# LinkS.net
KiCad netlist of a schematic drawn in Altium Designer
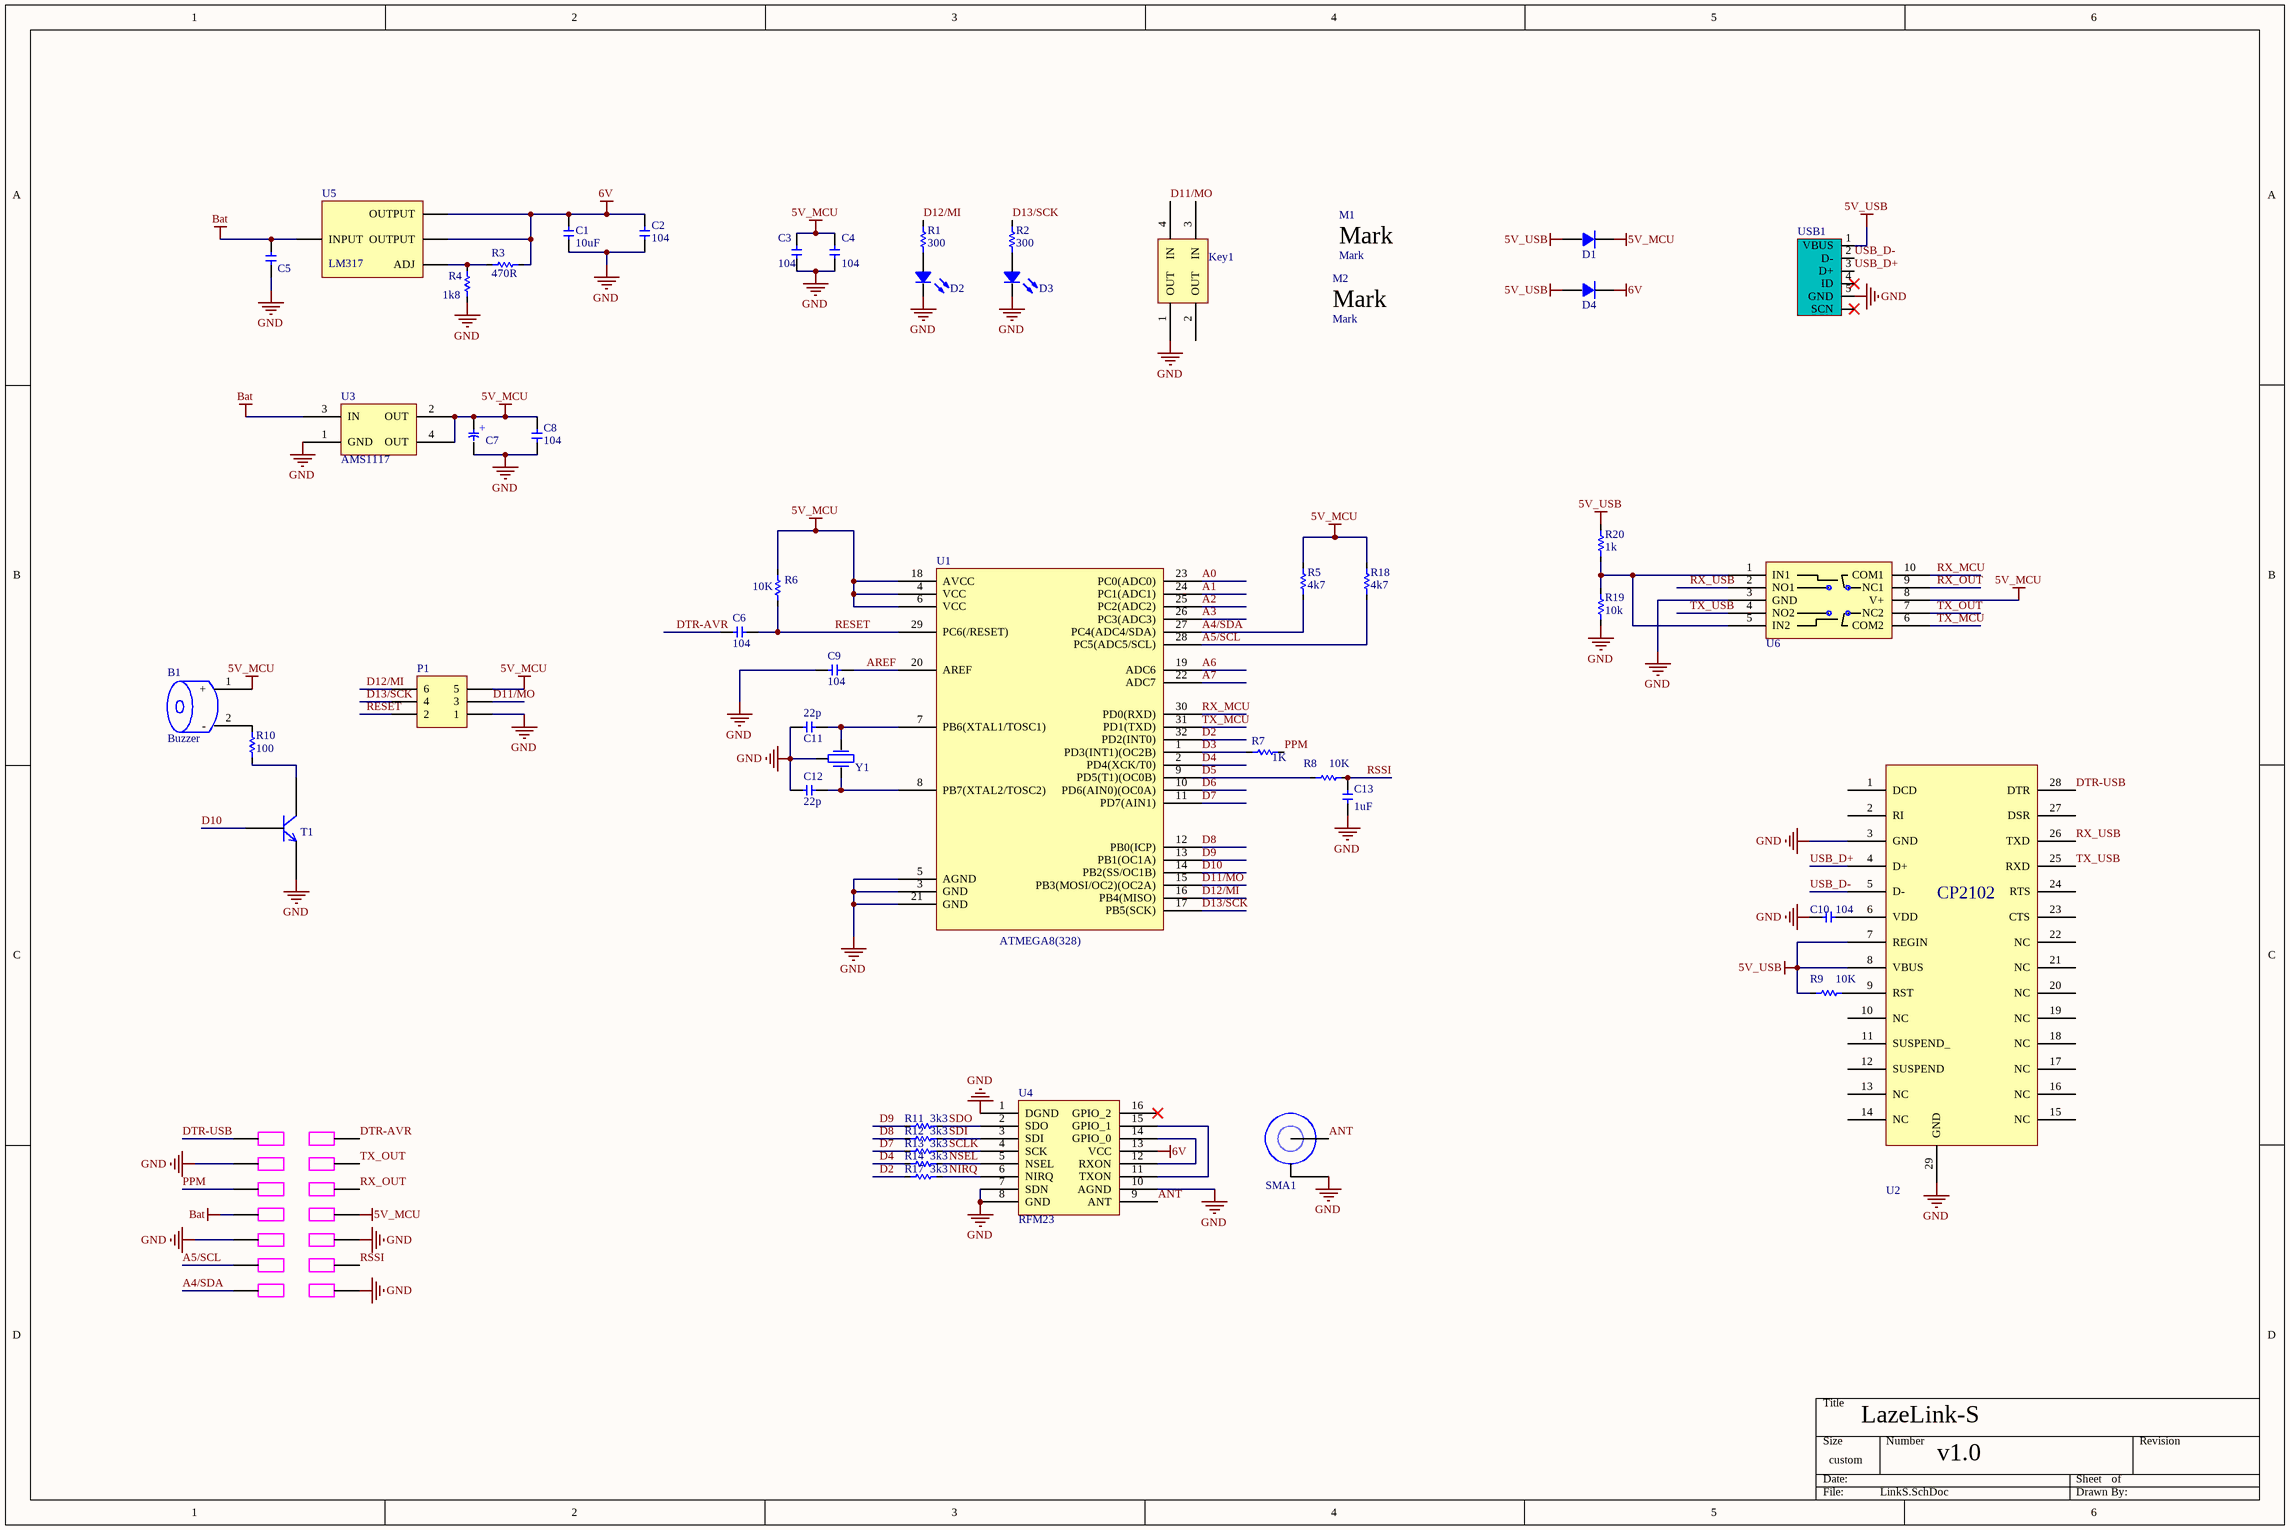
[diagram p0: LinkS.SchDoc]

(export (version "E")
  (design (tool "Eeschema 10.0.6"))
  (components
    (comp (ref "B1") (value "Buzzer") (footprint "BUZZER9055") (libsource (lib "Drone") (part "Buzzer")))
    (comp (ref "C1")
      (value "10uF")
      (footprint "1206 CAP")
      (description "Capacitor")
      (fields (field (name "PUBLISHER") "Altium Limited"))
      (libsource (lib "Drone") (part "CAP"))
    )
    (comp (ref "C2")
      (value "104")
      (footprint "0603 CAP")
      (description "Capacitor")
      (fields (field (name "PUBLISHER") "Altium Limited"))
      (libsource (lib "Drone") (part "CAP"))
    )
    (comp (ref "C3")
      (value "104")
      (footprint "0603 CAP")
      (description "Capacitor")
      (fields (field (name "PUBLISHER") "Altium Limited"))
      (libsource (lib "Drone") (part "CAP"))
    )
    (comp (ref "C4")
      (value "104")
      (footprint "0603 CAP")
      (description "Capacitor")
      (fields (field (name "PUBLISHER") "Altium Limited"))
      (libsource (lib "Drone") (part "CAP"))
    )
    (comp (ref "C5")
      (value "10uF")
      (footprint "1206")
      (description "Capacitor")
      (fields (field (name "PUBLISHER") "Altium Limited"))
      (libsource (lib "Drone") (part "CAP"))
    )
    (comp (ref "C6")
      (value "104")
      (footprint "0603 CAP")
      (description "Capacitor")
      (fields (field (name "PUBLISHER") "Altium Limited"))
      (libsource (lib "Drone") (part "CAP"))
    )
    (comp (ref "C7")
      (value "10uf")
      (footprint "1206 CAP")
      (description "Capacitor")
      (libsource (lib "Drone") (part "Cap Pol"))
    )
    (comp (ref "C8")
      (value "104")
      (footprint "0603 CAP")
      (description "Capacitor")
      (fields (field (name "PUBLISHER") "Altium Limited"))
      (libsource (lib "Drone") (part "CAP"))
    )
    (comp (ref "C9")
      (value "104")
      (footprint "0603 CAP")
      (description "Capacitor")
      (fields (field (name "PUBLISHER") "Altium Limited"))
      (libsource (lib "Drone") (part "CAP"))
    )
    (comp (ref "C10")
      (value "104")
      (footprint "0603 CAP")
      (description "Capacitor")
      (fields (field (name "PUBLISHER") "Altium Limited"))
      (libsource (lib "Drone") (part "CAP"))
    )
    (comp (ref "C11")
      (value "22p")
      (footprint "0603 CAP")
      (description "Capacitor")
      (fields (field (name "PUBLISHER") "Altium Limited"))
      (libsource (lib "Drone") (part "CAP"))
    )
    (comp (ref "C12")
      (value "22p")
      (footprint "0603 CAP")
      (description "Capacitor")
      (fields (field (name "PUBLISHER") "Altium Limited"))
      (libsource (lib "Drone") (part "CAP"))
    )
    (comp (ref "C13")
      (value "1uF")
      (footprint "0603 CAP")
      (description "Capacitor")
      (fields (field (name "PUBLISHER") "Altium Limited"))
      (libsource (lib "Drone") (part "CAP"))
    )
    (comp (ref "D1") (value "Diode") (footprint "DIODE-SOD123") (libsource (lib "Drone") (part "Diode")))
    (comp (ref "D2")
      (value "LED")
      (footprint "0805 LED")
      (description "Typical RED, GREEN, YELLOW, AMBER GaAs LED")
      (fields (field (name "PUBLISHER") "Altium Limited"))
      (libsource (lib "Drone") (part "LED"))
    )
    (comp (ref "D3")
      (value "LED")
      (footprint "0805 LED")
      (description "Typical RED, GREEN, YELLOW, AMBER GaAs LED")
      (fields (field (name "PUBLISHER") "Altium Limited"))
      (libsource (lib "Drone") (part "LED"))
    )
    (comp (ref "D4") (value "Diode") (footprint "DIODE-SOD123") (libsource (lib "Drone") (part "Diode")))
    (comp (ref "Key1")
      (value "KeySMT")
      (footprint "KEY SMT BIGGER")
      (libsource (lib "Drone") (part "KeySMT"))
    )
    (comp (ref "M1") (value "Mark") (footprint "MarkPoint") (libsource (lib "Drone") (part "Mark")))
    (comp (ref "M2") (value "Mark") (footprint "MarkPoint") (libsource (lib "Drone") (part "Mark")))
    (comp (ref "P1")
      (value "Header 3X2")
      (footprint "HDR2X3")
      (description "Header, 3-Pin, Dual row")
      (fields (field (name "PUBLISHER") "Altium Limited"))
      (libsource (lib "Miscellaneous Connectors") (part "Header 3X2"))
    )
    (comp (ref "Pad1") (value "EdgePad") (footprint "edgepad") (libsource (lib "Drone") (part "EdgePad")))
    (comp (ref "Pad2") (value "EdgePad") (footprint "edgepad") (libsource (lib "") (part "EdgePad_1")))
    (comp (ref "Pad3") (value "EdgePad") (footprint "edgepad") (libsource (lib "Drone") (part "EdgePad")))
    (comp (ref "Pad4") (value "EdgePad") (footprint "edgepad") (libsource (lib "") (part "EdgePad_1")))
    (comp (ref "Pad5") (value "EdgePad") (footprint "edgepad") (libsource (lib "Drone") (part "EdgePad")))
    (comp (ref "Pad6") (value "EdgePad") (footprint "edgepad") (libsource (lib "") (part "EdgePad_1")))
    (comp (ref "Pad7") (value "EdgePad") (footprint "edgepad") (libsource (lib "Drone") (part "EdgePad")))
    (comp (ref "Pad8") (value "EdgePad") (footprint "edgepad") (libsource (lib "") (part "EdgePad_1")))
    (comp (ref "Pad9") (value "EdgePad") (footprint "edgepad") (libsource (lib "Drone") (part "EdgePad")))
    (comp (ref "Pad10") (value "EdgePad") (footprint "edgepad") (libsource (lib "") (part "EdgePad_1")))
    (comp (ref "Pad11") (value "EdgePad") (footprint "edgepad") (libsource (lib "Drone") (part "EdgePad")))
    (comp (ref "Pad12") (value "EdgePad") (footprint "edgepad") (libsource (lib "") (part "EdgePad_1")))
    (comp (ref "Pad13") (value "EdgePad") (footprint "edgepad") (libsource (lib "Drone") (part "EdgePad")))
    (comp (ref "Pad14") (value "EdgePad") (footprint "edgepad") (libsource (lib "") (part "EdgePad_1")))
    (comp (ref "R1")
      (value "300")
      (footprint "0603 RES")
      (description "Resistor")
      (fields (field (name "PUBLISHER") "Altium Limited"))
      (libsource (lib "Drone") (part "Res"))
    )
    (comp (ref "R2")
      (value "300")
      (footprint "0603 RES")
      (description "Resistor")
      (fields (field (name "PUBLISHER") "Altium Limited"))
      (libsource (lib "Drone") (part "Res"))
    )
    (comp (ref "R3")
      (value "470R")
      (footprint "0603 RES")
      (description "Resistor")
      (fields (field (name "PUBLISHER") "Altium Limited"))
      (libsource (lib "Drone") (part "Res"))
    )
    (comp (ref "R4")
      (value "1k8")
      (footprint "0603 RES")
      (description "Resistor")
      (fields (field (name "PUBLISHER") "Altium Limited"))
      (libsource (lib "Drone") (part "Res"))
    )
    (comp (ref "R5")
      (value "4k7")
      (footprint "0603 RES")
      (description "Resistor")
      (fields (field (name "PUBLISHER") "Altium Limited"))
      (libsource (lib "Drone") (part "Res"))
    )
    (comp (ref "R6")
      (value "10K")
      (footprint "0603 RES")
      (description "Resistor")
      (fields (field (name "PUBLISHER") "Altium Limited"))
      (libsource (lib "Drone") (part "Res"))
    )
    (comp (ref "R7")
      (value "1K")
      (footprint "0603 RES")
      (description "Resistor")
      (fields (field (name "PUBLISHER") "Altium Limited"))
      (libsource (lib "Drone") (part "Res"))
    )
    (comp (ref "R8")
      (value "10K")
      (footprint "0603 RES")
      (description "Resistor")
      (fields (field (name "PUBLISHER") "Altium Limited"))
      (libsource (lib "Drone") (part "Res"))
    )
    (comp (ref "R9")
      (value "10K")
      (footprint "0603 RES")
      (description "Resistor")
      (fields (field (name "PUBLISHER") "Altium Limited"))
      (libsource (lib "Drone") (part "Res"))
    )
    (comp (ref "R10")
      (value "100")
      (footprint "0603 RES")
      (description "Resistor")
      (fields (field (name "PUBLISHER") "Altium Limited"))
      (libsource (lib "Drone") (part "Res"))
    )
    (comp (ref "R11")
      (value "3k3")
      (footprint "0603 RES")
      (description "Resistor")
      (fields (field (name "PUBLISHER") "Altium Limited"))
      (libsource (lib "Drone") (part "Res"))
    )
    (comp (ref "R12")
      (value "3k3")
      (footprint "0603 RES")
      (description "Resistor")
      (fields (field (name "PUBLISHER") "Altium Limited"))
      (libsource (lib "Drone") (part "Res"))
    )
    (comp (ref "R13")
      (value "3k3")
      (footprint "0603 RES")
      (description "Resistor")
      (fields (field (name "PUBLISHER") "Altium Limited"))
      (libsource (lib "Drone") (part "Res"))
    )
    (comp (ref "R14")
      (value "3k3")
      (footprint "0603 RES")
      (description "Resistor")
      (fields (field (name "PUBLISHER") "Altium Limited"))
      (libsource (lib "Drone") (part "Res"))
    )
    (comp (ref "R17")
      (value "3k3")
      (footprint "0603 RES")
      (description "Resistor")
      (fields (field (name "PUBLISHER") "Altium Limited"))
      (libsource (lib "Drone") (part "Res"))
    )
    (comp (ref "R18")
      (value "4k7")
      (footprint "0603 RES")
      (description "Resistor")
      (fields (field (name "PUBLISHER") "Altium Limited"))
      (libsource (lib "Drone") (part "Res"))
    )
    (comp (ref "R19")
      (value "10k")
      (footprint "0603 RES")
      (description "Resistor")
      (fields (field (name "PUBLISHER") "Altium Limited"))
      (libsource (lib "Drone") (part "Res"))
    )
    (comp (ref "R20")
      (value "1k")
      (footprint "0603 RES")
      (description "Resistor")
      (fields (field (name "PUBLISHER") "Altium Limited"))
      (libsource (lib "Drone") (part "Res"))
    )
    (comp (ref "SMA1") (value "SMA Base") (footprint "ANT SMA") (libsource (lib "Drone") (part "SMA Base")))
    (comp (ref "T1") (value "NPN") (footprint "NPN-SOT-23B_M") (libsource (lib "Drone") (part "NPN")))
    (comp (ref "U1")
      (value "ATmega328")
      (footprint "ATMEGA328FIX")
      (libsource (lib "Drone") (part "ATmega328"))
    )
    (comp (ref "U2") (value "CP2102") (footprint "CP2102") (libsource (lib "Drone") (part "CP2102")))
    (comp (ref "U3")
      (value "AMS1117")
      (footprint "ams1117")
      (description "1117")
      (libsource (lib "Drone") (part "AMS1117"))
    )
    (comp (ref "U4") (value "RFM23") (footprint "RFM23MODULE") (libsource (lib "Drone") (part "RFM23")))
    (comp (ref "U5") (value "LM317") (footprint "SOT230P700X180-4N") (libsource (lib "Drone") (part "LM317")))
    (comp (ref "U6") (value "TS5A23157") (footprint "TS5A23157") (libsource (lib "Drone") (part "TS5A23157")))
    (comp (ref "USB1")
      (value "USB")
      (footprint "MINI USB A")
      (description "USB Type-B SMT Socket")
      (libsource (lib "Drone") (part "USB_SMT_B"))
    )
    (comp (ref "Y1")
      (value "Crystal3Foot")
      (footprint "Crystal3Foot")
      (libsource (lib "Drone") (part "Crystal3Foot"))
    )
  )
  (nets
    (net (code "1") (name "/A0") (class "Default")
      (node (ref "U1") (pin "23") (pinfunction "PC0(ADC0)_23") (pintype "passive"))
    )
    (net (code "2") (name "/A1") (class "Default")
      (node (ref "U1") (pin "24") (pinfunction "PC1(ADC1)_24") (pintype "passive"))
    )
    (net (code "3") (name "/A2") (class "Default")
      (node (ref "U1") (pin "25") (pinfunction "PC2(ADC2)_25") (pintype "passive"))
    )
    (net (code "4") (name "/A3") (class "Default")
      (node (ref "U1") (pin "26") (pinfunction "PC3(ADC3)_26") (pintype "passive"))
    )
    (net (code "5") (name "/A4{slash}SDA") (class "Default")
      (node (ref "Pad13") (pin "1") (pinfunction "1_1") (pintype "passive"))
      (node (ref "R5") (pin "1") (pinfunction "1_1") (pintype "passive"))
      (node (ref "U1") (pin "27") (pinfunction "PC4(ADC4/SDA)_27") (pintype "passive"))
    )
    (net (code "6") (name "/A5{slash}SCL") (class "Default")
      (node (ref "Pad11") (pin "1") (pinfunction "1_1") (pintype "passive"))
      (node (ref "R18") (pin "1") (pinfunction "1_1") (pintype "passive"))
      (node (ref "U1") (pin "28") (pinfunction "PC5(ADC5/SCL)_28") (pintype "passive"))
    )
    (net (code "7") (name "/A6") (class "Default")
      (node (ref "U1") (pin "19") (pinfunction "ADC6_19") (pintype "passive"))
    )
    (net (code "8") (name "/A7") (class "Default")
      (node (ref "U1") (pin "22") (pinfunction "ADC7_22") (pintype "passive"))
    )
    (net (code "9") (name "/ANT") (class "Default")
      (node (ref "SMA1") (pin "1") (pinfunction "Ant_1") (pintype "passive"))
      (node (ref "U4") (pin "9") (pinfunction "ANT_9") (pintype "passive"))
    )
    (net (code "10") (name "/AREF") (class "Default")
      (node (ref "C9") (pin "1") (pinfunction "1_1") (pintype "passive"))
      (node (ref "U1") (pin "20") (pinfunction "AREF_20") (pintype "passive"))
    )
    (net (code "11") (name "/D2") (class "Default")
      (node (ref "R17") (pin "2") (pinfunction "2_2") (pintype "passive"))
      (node (ref "U1") (pin "32") (pinfunction "PD2(INT0)_32") (pintype "passive"))
    )
    (net (code "12") (name "/D3") (class "Default")
      (node (ref "R7") (pin "2") (pinfunction "2_2") (pintype "passive"))
      (node (ref "U1") (pin "1") (pinfunction "PD3(INT1)(OC2B)_1") (pintype "passive"))
    )
    (net (code "13") (name "/D4") (class "Default")
      (node (ref "R14") (pin "2") (pinfunction "2_2") (pintype "passive"))
      (node (ref "U1") (pin "2") (pinfunction "PD4(XCK/T0)_2") (pintype "passive"))
    )
    (net (code "14") (name "/D5") (class "Default")
      (node (ref "R8") (pin "2") (pinfunction "2_2") (pintype "passive"))
      (node (ref "U1") (pin "9") (pinfunction "PD5(T1)(OC0B)_9") (pintype "passive"))
    )
    (net (code "15") (name "/D6") (class "Default")
      (node (ref "U1") (pin "10") (pinfunction "PD6(AIN0)(OC0A)_10") (pintype "passive"))
    )
    (net (code "16") (name "/D7") (class "Default")
      (node (ref "R13") (pin "2") (pinfunction "2_2") (pintype "passive"))
      (node (ref "U1") (pin "11") (pinfunction "PD7(AIN1)_11") (pintype "passive"))
    )
    (net (code "17") (name "/D8") (class "Default")
      (node (ref "R12") (pin "2") (pinfunction "2_2") (pintype "passive"))
      (node (ref "U1") (pin "12") (pinfunction "PB0(ICP)_12") (pintype "passive"))
    )
    (net (code "18") (name "/D9") (class "Default")
      (node (ref "R11") (pin "2") (pinfunction "2_2") (pintype "passive"))
      (node (ref "U1") (pin "13") (pinfunction "PB1(OC1A)_13") (pintype "passive"))
    )
    (net (code "19") (name "/D10") (class "Default")
      (node (ref "T1") (pin "1") (pinfunction "Sig_1") (pintype "passive"))
      (node (ref "U1") (pin "14") (pinfunction "PB2(SS/OC1B)_14") (pintype "passive"))
    )
    (net (code "20") (name "/D11{slash}MO") (class "Default")
      (node (ref "Key1") (pin "4") (pinfunction "IN_4") (pintype "passive"))
      (node (ref "P1") (pin "3") (pinfunction "3_3") (pintype "passive"))
      (node (ref "U1") (pin "15") (pinfunction "PB3(MOSI/OC2)(OC2A)_15") (pintype "passive"))
    )
    (net (code "21") (name "/D12{slash}MI") (class "Default")
      (node (ref "P1") (pin "6") (pinfunction "6_6") (pintype "passive"))
      (node (ref "R1") (pin "1") (pinfunction "1_1") (pintype "passive"))
      (node (ref "U1") (pin "16") (pinfunction "PB4(MISO)_16") (pintype "passive"))
    )
    (net (code "22") (name "/D13{slash}SCK") (class "Default")
      (node (ref "P1") (pin "4") (pinfunction "4_4") (pintype "passive"))
      (node (ref "R2") (pin "1") (pinfunction "1_1") (pintype "passive"))
      (node (ref "U1") (pin "17") (pinfunction "PB5(SCK)_17") (pintype "passive"))
    )
    (net (code "23") (name "/DTR-AVR") (class "Default")
      (node (ref "C6") (pin "2") (pinfunction "2_2") (pintype "passive"))
      (node (ref "Pad2") (pin "1") (pinfunction "1_1") (pintype "passive"))
    )
    (net (code "24") (name "/DTR-USB") (class "Default")
      (node (ref "Pad1") (pin "1") (pinfunction "1_1") (pintype "passive"))
      (node (ref "U2") (pin "28") (pinfunction "DTR_28") (pintype "passive"))
    )
    (net (code "25") (name "/NIRQ") (class "Default")
      (node (ref "R17") (pin "1") (pinfunction "1_1") (pintype "passive"))
      (node (ref "U4") (pin "6") (pinfunction "NIRQ_6") (pintype "passive"))
    )
    (net (code "26") (name "/NSEL") (class "Default")
      (node (ref "R14") (pin "1") (pinfunction "1_1") (pintype "passive"))
      (node (ref "U4") (pin "5") (pinfunction "NSEL_5") (pintype "passive"))
    )
    (net (code "27") (name "/PPM") (class "Default")
      (node (ref "Pad5") (pin "1") (pinfunction "1_1") (pintype "passive"))
      (node (ref "R7") (pin "1") (pinfunction "1_1") (pintype "passive"))
    )
    (net (code "28") (name "/RESET") (class "Default")
      (node (ref "C6") (pin "1") (pinfunction "1_1") (pintype "passive"))
      (node (ref "P1") (pin "2") (pinfunction "2_2") (pintype "passive"))
      (node (ref "R6") (pin "1") (pinfunction "1_1") (pintype "passive"))
      (node (ref "U1") (pin "29") (pinfunction "PC6(/RESET)_29") (pintype "passive"))
    )
    (net (code "29") (name "/RSSI") (class "Default")
      (node (ref "C13") (pin "2") (pinfunction "2_2") (pintype "passive"))
      (node (ref "Pad12") (pin "1") (pinfunction "1_1") (pintype "passive"))
      (node (ref "R8") (pin "1") (pinfunction "1_1") (pintype "passive"))
    )
    (net (code "30") (name "/RX_MCU") (class "Default")
      (node (ref "U1") (pin "30") (pinfunction "PD0(RXD)_30") (pintype "passive"))
      (node (ref "U6") (pin "10") (pinfunction "COM1_10") (pintype "passive"))
    )
    (net (code "31") (name "/RX_OUT") (class "Default")
      (node (ref "Pad6") (pin "1") (pinfunction "1_1") (pintype "passive"))
      (node (ref "U6") (pin "9") (pinfunction "NC1_9") (pintype "passive"))
    )
    (net (code "32") (name "/RX_USB") (class "Default")
      (node (ref "U2") (pin "26") (pinfunction "TXD_26") (pintype "passive"))
      (node (ref "U6") (pin "2") (pinfunction "NO1_2") (pintype "passive"))
    )
    (net (code "33") (name "/SCLK") (class "Default")
      (node (ref "R13") (pin "1") (pinfunction "1_1") (pintype "passive"))
      (node (ref "U4") (pin "4") (pinfunction "SCK_4") (pintype "passive"))
    )
    (net (code "34") (name "/SDI") (class "Default")
      (node (ref "R12") (pin "1") (pinfunction "1_1") (pintype "passive"))
      (node (ref "U4") (pin "3") (pinfunction "SDI_3") (pintype "passive"))
    )
    (net (code "35") (name "/SDO") (class "Default")
      (node (ref "R11") (pin "1") (pinfunction "1_1") (pintype "passive"))
      (node (ref "U4") (pin "2") (pinfunction "SDO_2") (pintype "passive"))
    )
    (net (code "36") (name "/TX_MCU") (class "Default")
      (node (ref "U1") (pin "31") (pinfunction "PD1(TXD)_31") (pintype "passive"))
      (node (ref "U6") (pin "6") (pinfunction "COM2_6") (pintype "passive"))
    )
    (net (code "37") (name "/TX_OUT") (class "Default")
      (node (ref "Pad4") (pin "1") (pinfunction "1_1") (pintype "passive"))
      (node (ref "U6") (pin "7") (pinfunction "NC2_7") (pintype "passive"))
    )
    (net (code "38") (name "/TX_USB") (class "Default")
      (node (ref "U2") (pin "25") (pinfunction "RXD_25") (pintype "passive"))
      (node (ref "U6") (pin "4") (pinfunction "NO2_4") (pintype "passive"))
    )
    (net (code "39") (name "/USB_D+") (class "Default")
      (node (ref "U2") (pin "4") (pinfunction "D+_4") (pintype "passive"))
      (node (ref "USB1") (pin "3") (pinfunction "D+_3") (pintype "passive"))
    )
    (net (code "40") (name "/USB_D-") (class "Default")
      (node (ref "U2") (pin "5") (pinfunction "D-_5") (pintype "passive"))
      (node (ref "USB1") (pin "2") (pinfunction "D-_2") (pintype "passive"))
    )
    (net (code "41") (name "5V_MCU") (class "Default")
      (node (ref "B1") (pin "1") (pinfunction "+_1") (pintype "passive"))
      (node (ref "C3") (pin "1") (pinfunction "1_1") (pintype "passive"))
      (node (ref "C4") (pin "1") (pinfunction "1_1") (pintype "passive"))
      (node (ref "C7") (pin "1") (pinfunction "A_1") (pintype "passive"))
      (node (ref "C8") (pin "1") (pinfunction "1_1") (pintype "passive"))
      (node (ref "D1") (pin "2") (pinfunction "B_2") (pintype "passive"))
      (node (ref "P1") (pin "5") (pinfunction "5_5") (pintype "passive"))
      (node (ref "Pad8") (pin "1") (pinfunction "1_1") (pintype "passive"))
      (node (ref "R18") (pin "2") (pinfunction "2_2") (pintype "passive"))
      (node (ref "R5") (pin "2") (pinfunction "2_2") (pintype "passive"))
      (node (ref "R6") (pin "2") (pinfunction "2_2") (pintype "passive"))
      (node (ref "U1") (pin "18") (pinfunction "AVCC_18") (pintype "passive"))
      (node (ref "U1") (pin "4") (pinfunction "VCC_4") (pintype "passive"))
      (node (ref "U1") (pin "6") (pinfunction "VCC_6") (pintype "passive"))
      (node (ref "U3") (pin "2") (pinfunction "OUT_2") (pintype "passive"))
      (node (ref "U3") (pin "4") (pinfunction "OUT_4") (pintype "passive"))
      (node (ref "U6") (pin "8") (pinfunction "V+_8") (pintype "passive"))
    )
    (net (code "42") (name "5V_USB") (class "Default")
      (node (ref "D1") (pin "1") (pinfunction "A_1") (pintype "passive"))
      (node (ref "D4") (pin "1") (pinfunction "A_1") (pintype "passive"))
      (node (ref "R20") (pin "2") (pinfunction "2_2") (pintype "passive"))
      (node (ref "R9") (pin "2") (pinfunction "2_2") (pintype "passive"))
      (node (ref "U2") (pin "7") (pinfunction "REGIN_7") (pintype "passive"))
      (node (ref "U2") (pin "8") (pinfunction "VBUS_8") (pintype "passive"))
      (node (ref "USB1") (pin "1") (pinfunction "VBUS_1") (pintype "passive"))
    )
    (net (code "43") (name "6V") (class "Default")
      (node (ref "C1") (pin "1") (pinfunction "1_1") (pintype "passive"))
      (node (ref "C2") (pin "1") (pinfunction "1_1") (pintype "passive"))
      (node (ref "D4") (pin "2") (pinfunction "B_2") (pintype "passive"))
      (node (ref "R3") (pin "1") (pinfunction "1_1") (pintype "passive"))
      (node (ref "U4") (pin "13") (pinfunction "VCC_13") (pintype "passive"))
      (node (ref "U5") (pin "2") (pinfunction "OUTPUT_2") (pintype "passive"))
      (node (ref "U5") (pin "4") (pinfunction "OUTPUT_4") (pintype "passive"))
    )
    (net (code "44") (name "Bat") (class "Default")
      (node (ref "C5") (pin "2") (pinfunction "2_2") (pintype "passive"))
      (node (ref "Pad7") (pin "1") (pinfunction "1_1") (pintype "passive"))
      (node (ref "U3") (pin "3") (pinfunction "IN_3") (pintype "passive"))
      (node (ref "U5") (pin "3") (pinfunction "INPUT_3") (pintype "passive"))
    )
    (net (code "45") (name "GND") (class "Default")
      (node (ref "C1") (pin "2") (pinfunction "2_2") (pintype "passive"))
      (node (ref "C10") (pin "1") (pinfunction "1_1") (pintype "passive"))
      (node (ref "C11") (pin "1") (pinfunction "1_1") (pintype "passive"))
      (node (ref "C12") (pin "1") (pinfunction "1_1") (pintype "passive"))
      (node (ref "C13") (pin "1") (pinfunction "1_1") (pintype "passive"))
      (node (ref "C2") (pin "2") (pinfunction "2_2") (pintype "passive"))
      (node (ref "C3") (pin "2") (pinfunction "2_2") (pintype "passive"))
      (node (ref "C4") (pin "2") (pinfunction "2_2") (pintype "passive"))
      (node (ref "C5") (pin "1") (pinfunction "1_1") (pintype "passive"))
      (node (ref "C7") (pin "2") (pinfunction "B_2") (pintype "passive"))
      (node (ref "C8") (pin "2") (pinfunction "2_2") (pintype "passive"))
      (node (ref "C9") (pin "2") (pinfunction "2_2") (pintype "passive"))
      (node (ref "D2") (pin "2") (pinfunction "K_2") (pintype "passive"))
      (node (ref "D3") (pin "2") (pinfunction "K_2") (pintype "passive"))
      (node (ref "Key1") (pin "1") (pinfunction "OUT_1") (pintype "passive"))
      (node (ref "P1") (pin "1") (pinfunction "1_1") (pintype "passive"))
      (node (ref "Pad10") (pin "1") (pinfunction "1_1") (pintype "passive"))
      (node (ref "Pad14") (pin "1") (pinfunction "1_1") (pintype "passive"))
      (node (ref "Pad3") (pin "1") (pinfunction "1_1") (pintype "passive"))
      (node (ref "Pad9") (pin "1") (pinfunction "1_1") (pintype "passive"))
      (node (ref "R19") (pin "1") (pinfunction "1_1") (pintype "passive"))
      (node (ref "R4") (pin "2") (pinfunction "2_2") (pintype "passive"))
      (node (ref "SMA1") (pin "2") (pinfunction "Gnd_2") (pintype "passive"))
      (node (ref "T1") (pin "2") (pinfunction "Gnd_2") (pintype "passive"))
      (node (ref "U1") (pin "21") (pinfunction "GND_21") (pintype "passive"))
      (node (ref "U1") (pin "3") (pinfunction "GND_3") (pintype "passive"))
      (node (ref "U1") (pin "5") (pinfunction "AGND_5") (pintype "passive"))
      (node (ref "U2") (pin "29") (pinfunction "GND_29") (pintype "passive"))
      (node (ref "U2") (pin "3") (pinfunction "GND_3") (pintype "passive"))
      (node (ref "U3") (pin "1") (pinfunction "GND_1") (pintype "passive"))
      (node (ref "U4") (pin "1") (pinfunction "DGND_1") (pintype "passive"))
      (node (ref "U4") (pin "10") (pinfunction "AGND_10") (pintype "passive"))
      (node (ref "U4") (pin "7") (pinfunction "SDN_7") (pintype "passive"))
      (node (ref "U4") (pin "8") (pinfunction "GND_8") (pintype "passive"))
      (node (ref "U6") (pin "3") (pinfunction "GND_3") (pintype "passive"))
      (node (ref "USB1") (pin "5") (pinfunction "GND_5") (pintype "passive"))
      (node (ref "Y1") (pin "2") (pinfunction "2_2") (pintype "passive"))
    )
    (net (code "46") (name "Net-(B1--)") (class "Default")
      (node (ref "B1") (pin "2") (pinfunction "-_2") (pintype "passive"))
      (node (ref "R10") (pin "1") (pinfunction "1_1") (pintype "passive"))
    )
    (net (code "47") (name "Net-(D2-A)") (class "Default")
      (node (ref "D2") (pin "1") (pinfunction "A_1") (pintype "passive"))
      (node (ref "R1") (pin "2") (pinfunction "2_2") (pintype "passive"))
    )
    (net (code "48") (name "Net-(D3-A)") (class "Default")
      (node (ref "D3") (pin "1") (pinfunction "A_1") (pintype "passive"))
      (node (ref "R2") (pin "2") (pinfunction "2_2") (pintype "passive"))
    )
    (net (code "49") (name "Net-(T1-Collector)") (class "Default")
      (node (ref "R10") (pin "2") (pinfunction "2_2") (pintype "passive"))
      (node (ref "T1") (pin "3") (pinfunction "Collector_3") (pintype "passive"))
    )
    (net (code "50") (name "Net-(U1-PB6(XTAL1{slash}TOSC1))") (class "Default")
      (node (ref "C11") (pin "2") (pinfunction "2_2") (pintype "passive"))
      (node (ref "U1") (pin "7") (pinfunction "PB6(XTAL1/TOSC1)_7") (pintype "passive"))
      (node (ref "Y1") (pin "1") (pinfunction "0_1") (pintype "passive"))
    )
    (net (code "51") (name "Net-(U1-PB7(XTAL2{slash}TOSC2))") (class "Default")
      (node (ref "C12") (pin "2") (pinfunction "2_2") (pintype "passive"))
      (node (ref "U1") (pin "8") (pinfunction "PB7(XTAL2/TOSC2)_8") (pintype "passive"))
      (node (ref "Y1") (pin "3") (pinfunction "1_3") (pintype "passive"))
    )
    (net (code "52") (name "Net-(U2-RST)") (class "Default")
      (node (ref "R9") (pin "1") (pinfunction "1_1") (pintype "passive"))
      (node (ref "U2") (pin "9") (pinfunction "RST_9") (pintype "passive"))
    )
    (net (code "53") (name "Net-(U2-VDD)") (class "Default")
      (node (ref "C10") (pin "2") (pinfunction "2_2") (pintype "passive"))
      (node (ref "U2") (pin "6") (pinfunction "VDD_6") (pintype "passive"))
    )
    (net (code "54") (name "Net-(U4-GPIO_0)") (class "Default")
      (node (ref "U4") (pin "12") (pinfunction "RXON_12") (pintype "passive"))
      (node (ref "U4") (pin "14") (pinfunction "GPIO_0_14") (pintype "passive"))
    )
    (net (code "55") (name "Net-(U4-GPIO_1)") (class "Default")
      (node (ref "U4") (pin "11") (pinfunction "TXON_11") (pintype "passive"))
      (node (ref "U4") (pin "15") (pinfunction "GPIO_1_15") (pintype "passive"))
    )
    (net (code "56") (name "Net-(U5-ADJ)") (class "Default")
      (node (ref "R3") (pin "2") (pinfunction "2_2") (pintype "passive"))
      (node (ref "R4") (pin "1") (pinfunction "1_1") (pintype "passive"))
      (node (ref "U5") (pin "1") (pinfunction "ADJ_1") (pintype "passive"))
    )
    (net (code "57") (name "Net-(U6-IN1)") (class "Default")
      (node (ref "R19") (pin "2") (pinfunction "2_2") (pintype "passive"))
      (node (ref "R20") (pin "1") (pinfunction "1_1") (pintype "passive"))
      (node (ref "U6") (pin "1") (pinfunction "IN1_1") (pintype "passive"))
      (node (ref "U6") (pin "5") (pinfunction "IN2_5") (pintype "passive"))
    )
    (net (code "58") (name "unconnected-(Key1-IN-Pad3)") (class "Default")
      (node (ref "Key1") (pin "3") (pinfunction "IN_3") (pintype "passive"))
    )
    (net (code "59") (name "unconnected-(Key1-OUT-Pad2)") (class "Default")
      (node (ref "Key1") (pin "2") (pinfunction "OUT_2") (pintype "passive"))
    )
    (net (code "60") (name "unconnected-(U2-CTS-Pad23)") (class "Default")
      (node (ref "U2") (pin "23") (pinfunction "CTS_23") (pintype "passive"))
    )
    (net (code "61") (name "unconnected-(U2-DCD-Pad1)") (class "Default")
      (node (ref "U2") (pin "1") (pinfunction "DCD_1") (pintype "passive"))
    )
    (net (code "62") (name "unconnected-(U2-DSR-Pad27)") (class "Default")
      (node (ref "U2") (pin "27") (pinfunction "DSR_27") (pintype "passive"))
    )
    (net (code "63") (name "unconnected-(U2-NC-Pad10)") (class "Default")
      (node (ref "U2") (pin "10") (pinfunction "NC_10") (pintype "passive"))
    )
    (net (code "64") (name "unconnected-(U2-NC-Pad13)") (class "Default")
      (node (ref "U2") (pin "13") (pinfunction "NC_13") (pintype "passive"))
    )
    (net (code "65") (name "unconnected-(U2-NC-Pad14)") (class "Default")
      (node (ref "U2") (pin "14") (pinfunction "NC_14") (pintype "passive"))
    )
    (net (code "66") (name "unconnected-(U2-NC-Pad15)") (class "Default")
      (node (ref "U2") (pin "15") (pinfunction "NC_15") (pintype "passive"))
    )
    (net (code "67") (name "unconnected-(U2-NC-Pad16)") (class "Default")
      (node (ref "U2") (pin "16") (pinfunction "NC_16") (pintype "passive"))
    )
    (net (code "68") (name "unconnected-(U2-NC-Pad17)") (class "Default")
      (node (ref "U2") (pin "17") (pinfunction "NC_17") (pintype "passive"))
    )
    (net (code "69") (name "unconnected-(U2-NC-Pad18)") (class "Default")
      (node (ref "U2") (pin "18") (pinfunction "NC_18") (pintype "passive"))
    )
    (net (code "70") (name "unconnected-(U2-NC-Pad19)") (class "Default")
      (node (ref "U2") (pin "19") (pinfunction "NC_19") (pintype "passive"))
    )
    (net (code "71") (name "unconnected-(U2-NC-Pad20)") (class "Default")
      (node (ref "U2") (pin "20") (pinfunction "NC_20") (pintype "passive"))
    )
    (net (code "72") (name "unconnected-(U2-NC-Pad21)") (class "Default")
      (node (ref "U2") (pin "21") (pinfunction "NC_21") (pintype "passive"))
    )
    (net (code "73") (name "unconnected-(U2-NC-Pad22)") (class "Default")
      (node (ref "U2") (pin "22") (pinfunction "NC_22") (pintype "passive"))
    )
    (net (code "74") (name "unconnected-(U2-RI-Pad2)") (class "Default")
      (node (ref "U2") (pin "2") (pinfunction "RI_2") (pintype "passive"))
    )
    (net (code "75") (name "unconnected-(U2-RTS-Pad24)") (class "Default")
      (node (ref "U2") (pin "24") (pinfunction "RTS_24") (pintype "passive"))
    )
    (net (code "76") (name "unconnected-(U2-SUSPEND-Pad12)") (class "Default")
      (node (ref "U2") (pin "12") (pinfunction "SUSPEND_12") (pintype "passive"))
    )
    (net (code "77") (name "unconnected-(U2-SUSPEND_-Pad11)") (class "Default")
      (node (ref "U2") (pin "11") (pinfunction "SUSPEND__11") (pintype "passive"))
    )
    (net (code "78") (name "unconnected-(U4-GPIO_2-Pad16)") (class "Default")
      (node (ref "U4") (pin "16") (pinfunction "GPIO_2_16") (pintype "passive+no_connect"))
    )
    (net (code "79") (name "unconnected-(USB1-ID-Pad4)") (class "Default")
      (node (ref "USB1") (pin "4") (pinfunction "ID_4") (pintype "passive+no_connect"))
    )
    (net (code "80") (name "unconnected-(USB1-SCN-Pad0)") (class "Default")
      (node (ref "USB1") (pin "0") (pinfunction "SCN_0") (pintype "passive+no_connect"))
    )
  )
)
